# dpsv2.net
KiCad netlist of a schematic drawn in EAGLE
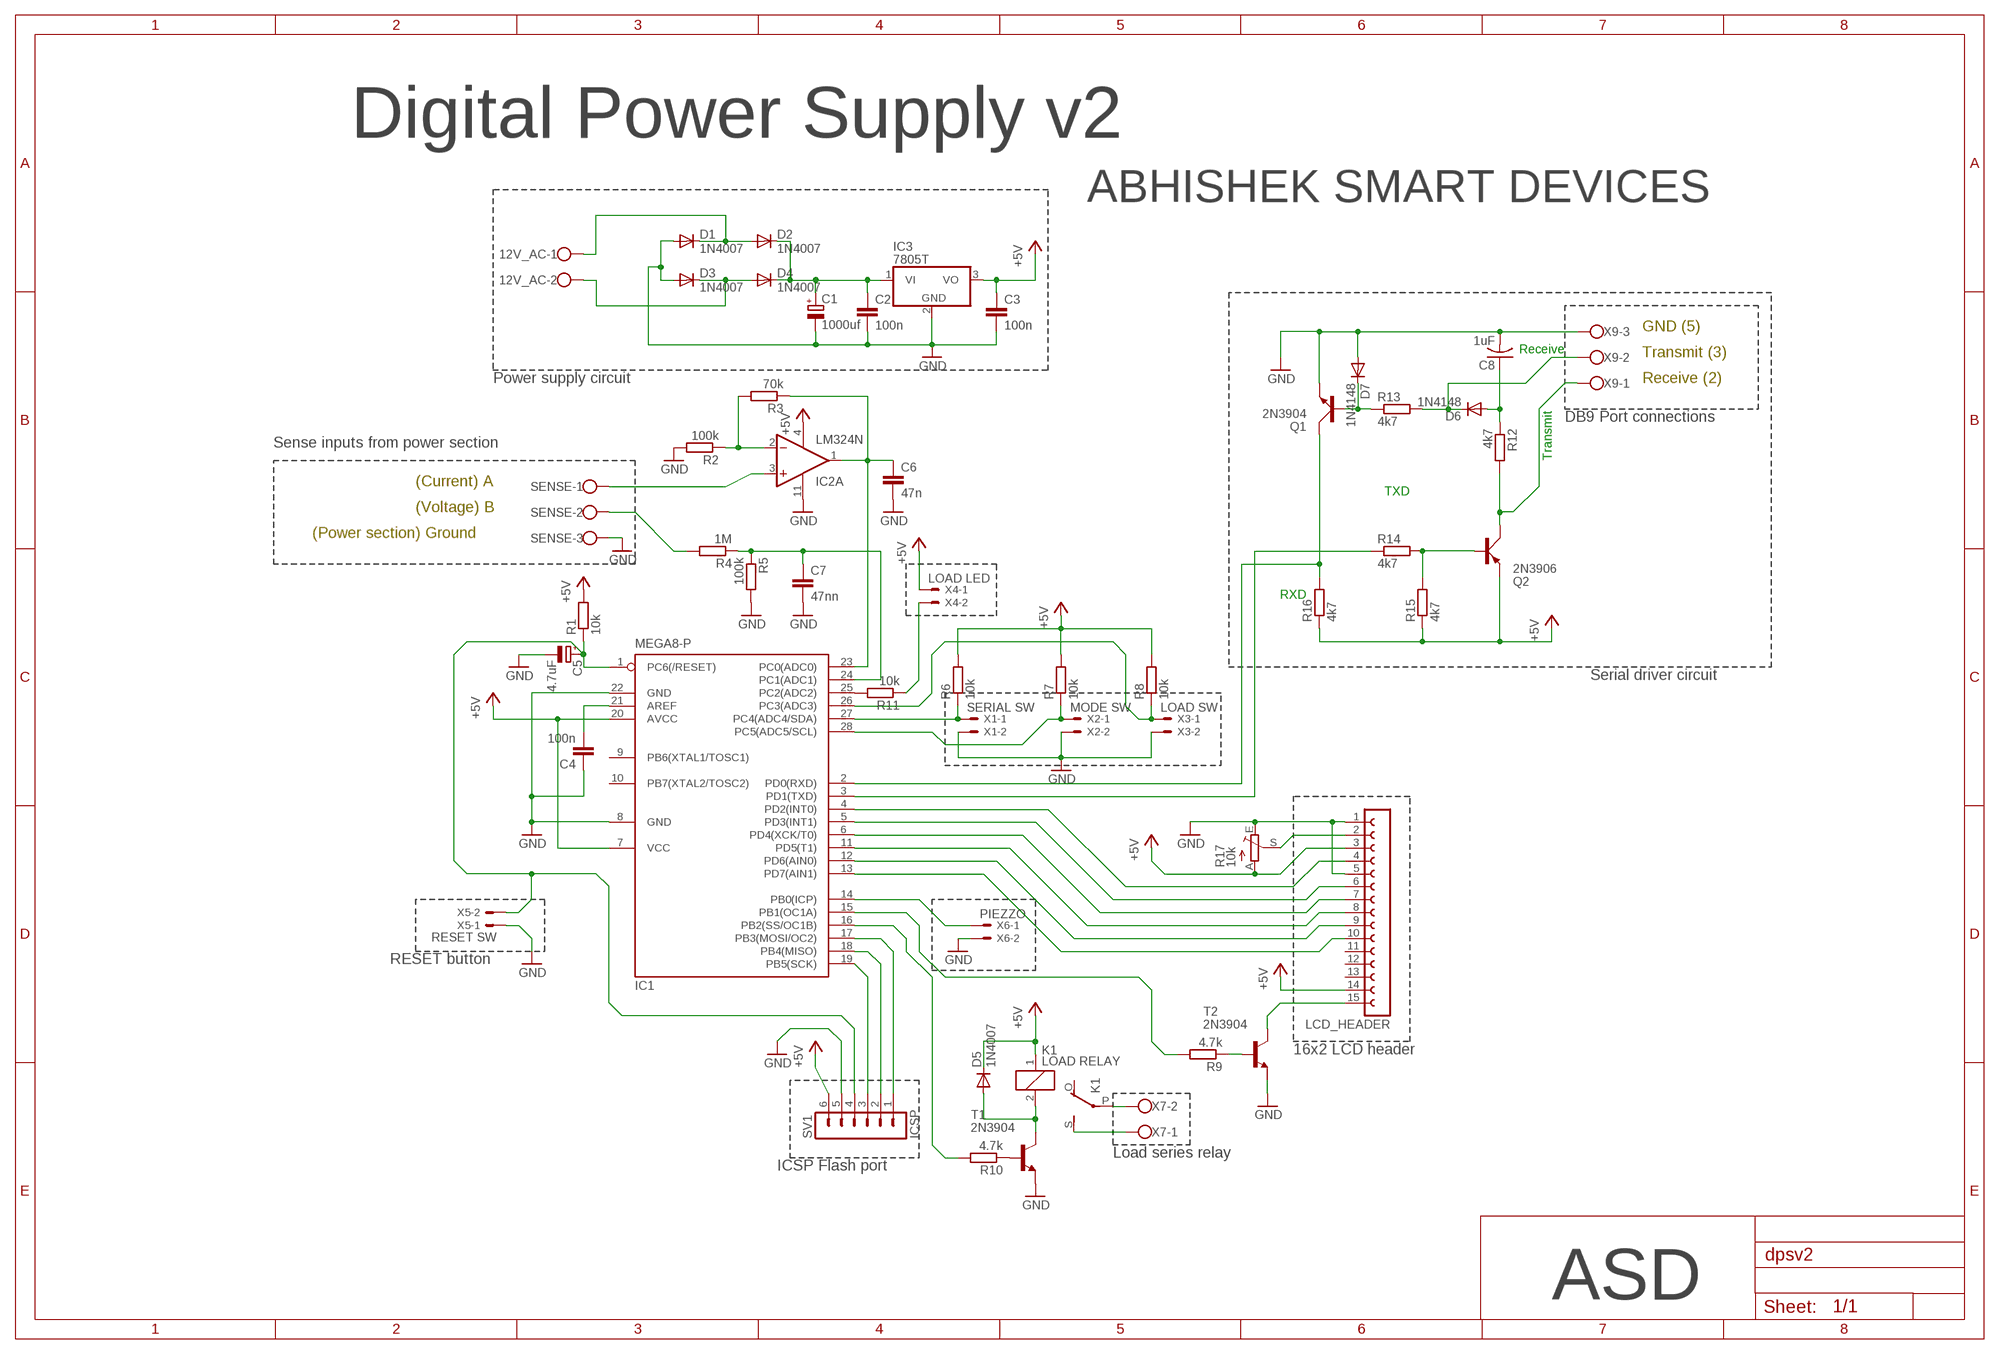
[diagram p0: schematic, sheet 1]

(export (version "E")
  (design (tool "Eeschema 10.0.6"))
  (components
    (comp (ref "12V_AC")
      (value "W237-102")
      (footprint "eagle-import:W237-102")
      (fields (field (name "MPN") "237-102"))
      (libsource (lib "eagle-import") (part "W237-102"))
    )
    (comp (ref "C1")
      (value "1000uf")
      (footprint "eagle-import:E5-13")
      (libsource (lib "eagle-import") (part "CPOL-EUE5-13"))
    )
    (comp (ref "C2")
      (value "100n")
      (footprint "eagle-import:C102-054X133")
      (libsource (lib "eagle-import") (part "C-EU102-054X133"))
    )
    (comp (ref "C3")
      (value "100n")
      (footprint "eagle-import:C102-054X133")
      (libsource (lib "eagle-import") (part "C-EU102-054X133"))
    )
    (comp (ref "C4")
      (value "100n")
      (footprint "eagle-import:C102-054X133")
      (libsource (lib "eagle-import") (part "C-EU102-054X133"))
    )
    (comp (ref "C5")
      (value "4.7uF")
      (footprint "eagle-import:E2,5-7")
      (libsource (lib "eagle-import") (part "CPOL-EUE2.5-7"))
    )
    (comp (ref "C6")
      (value "47n")
      (footprint "eagle-import:C050-025X075")
      (libsource (lib "eagle-import") (part "C-EU050-025X075"))
    )
    (comp (ref "C7")
      (value "47nn")
      (footprint "eagle-import:C050-025X075")
      (libsource (lib "eagle-import") (part "C-EU050-025X075"))
    )
    (comp (ref "C8")
      (value "1uF")
      (footprint "eagle-import:C025-040X050")
      (libsource (lib "eagle-import") (part "C-US025-040X050"))
    )
    (comp (ref "D1")
      (value "1N4007")
      (footprint "eagle-import:DO07")
      (libsource (lib "eagle-import") (part "DIODE-DO07"))
    )
    (comp (ref "D2")
      (value "1N4007")
      (footprint "eagle-import:DO07")
      (libsource (lib "eagle-import") (part "DIODE-DO07"))
    )
    (comp (ref "D3")
      (value "1N4007")
      (footprint "eagle-import:DO07")
      (libsource (lib "eagle-import") (part "DIODE-DO07"))
    )
    (comp (ref "D4")
      (value "1N4007")
      (footprint "eagle-import:DO07")
      (libsource (lib "eagle-import") (part "DIODE-DO07"))
    )
    (comp (ref "D5")
      (value "1N4007")
      (footprint "eagle-import:DO07")
      (libsource (lib "eagle-import") (part "DIODE-DO07"))
    )
    (comp (ref "D6")
      (value "1N4148")
      (footprint "eagle-import:DO35-10")
      (libsource (lib "eagle-import") (part "1N4148"))
    )
    (comp (ref "D7")
      (value "1N4148")
      (footprint "eagle-import:DO35-10")
      (libsource (lib "eagle-import") (part "1N4148"))
    )
    (comp (ref "IC1")
      (value "MEGA8-P")
      (footprint "eagle-import:DIL28-3")
      (libsource (lib "eagle-import") (part "MEGA8-P"))
    )
    (comp (ref "IC2")
      (value "LM324N")
      (footprint "eagle-import:DIL14")
      (libsource (lib "eagle-import") (part "LM324N"))
    )
    (comp (ref "IC3")
      (value "7805T")
      (footprint "eagle-import:TO220H")
      (libsource (lib "eagle-import") (part "78T05"))
    )
    (comp (ref "K1")
      (value "LOAD RELAY")
      (footprint "eagle-import:G5LE")
      (libsource (lib "eagle-import") (part "G5L"))
    )
    (comp (ref "LCD_HEADER")
      (value "FE15-1")
      (footprint "eagle-import:FE15")
      (libsource (lib "eagle-import") (part "FE15-1"))
    )
    (comp (ref "Q1")
      (value "2N3904")
      (footprint "eagle-import:TO92D")
      (libsource (lib "eagle-import") (part "2N3904"))
    )
    (comp (ref "Q2")
      (value "2N3906")
      (footprint "eagle-import:TO92D")
      (libsource (lib "eagle-import") (part "2N3906"))
    )
    (comp (ref "R1")
      (value "10k")
      (footprint "eagle-import:0309_12")
      (libsource (lib "eagle-import") (part "R-EU_0309/12"))
    )
    (comp (ref "R2")
      (value "100k")
      (footprint "eagle-import:0309_12")
      (libsource (lib "eagle-import") (part "R-EU_0309/12"))
    )
    (comp (ref "R3")
      (value "70k")
      (footprint "eagle-import:0309_12")
      (libsource (lib "eagle-import") (part "R-EU_0309/12"))
    )
    (comp (ref "R4")
      (value "1M")
      (footprint "eagle-import:0309_12")
      (libsource (lib "eagle-import") (part "R-EU_0309/12"))
    )
    (comp (ref "R5")
      (value "100k")
      (footprint "eagle-import:0309_12")
      (libsource (lib "eagle-import") (part "R-EU_0309/12"))
    )
    (comp (ref "R6")
      (value "10k")
      (footprint "eagle-import:0309_12")
      (libsource (lib "eagle-import") (part "R-EU_0309/12"))
    )
    (comp (ref "R7")
      (value "10k")
      (footprint "eagle-import:0309_12")
      (libsource (lib "eagle-import") (part "R-EU_0309/12"))
    )
    (comp (ref "R8")
      (value "10k")
      (footprint "eagle-import:0309_12")
      (libsource (lib "eagle-import") (part "R-EU_0309/12"))
    )
    (comp (ref "R9")
      (value "4.7k")
      (footprint "eagle-import:0309_12")
      (libsource (lib "eagle-import") (part "R-EU_0309/12"))
    )
    (comp (ref "R10")
      (value "4.7k")
      (footprint "eagle-import:0309_12")
      (libsource (lib "eagle-import") (part "R-EU_0309/12"))
    )
    (comp (ref "R11")
      (value "10k")
      (footprint "eagle-import:0309_12")
      (libsource (lib "eagle-import") (part "R-EU_0309/12"))
    )
    (comp (ref "R12")
      (value "4k7")
      (footprint "eagle-import:0309_12")
      (libsource (lib "eagle-import") (part "R-EU_0309/12"))
    )
    (comp (ref "R13")
      (value "4k7")
      (footprint "eagle-import:0309_12")
      (libsource (lib "eagle-import") (part "R-EU_0309/12"))
    )
    (comp (ref "R14")
      (value "4k7")
      (footprint "eagle-import:0309_12")
      (libsource (lib "eagle-import") (part "R-EU_0309/12"))
    )
    (comp (ref "R15")
      (value "4k7")
      (footprint "eagle-import:0309_12")
      (libsource (lib "eagle-import") (part "R-EU_0309/12"))
    )
    (comp (ref "R16")
      (value "4k7")
      (footprint "eagle-import:0309_12")
      (libsource (lib "eagle-import") (part "R-EU_0309/12"))
    )
    (comp (ref "R17")
      (value "10k")
      (footprint "eagle-import:B25X")
      (libsource (lib "eagle-import") (part "TRIM_EU-B25X"))
    )
    (comp (ref "SENSE")
      (value "W237-103")
      (footprint "eagle-import:W237-103")
      (fields (field (name "MPN") "237-103"))
      (libsource (lib "eagle-import") (part "W237-103"))
    )
    (comp (ref "SV1")
      (value "ICSP")
      (footprint "eagle-import:MA06-1")
      (libsource (lib "eagle-import") (part "MA06-1"))
    )
    (comp (ref "T1")
      (value "2N3904")
      (footprint "eagle-import:TO92-CBE")
      (libsource (lib "eagle-import") (part "-NPN-TO92-CBEBC548"))
    )
    (comp (ref "T2")
      (value "2N3904")
      (footprint "eagle-import:TO92-CBE")
      (libsource (lib "eagle-import") (part "-NPN-TO92-CBEBC548"))
    )
    (comp (ref "X1")
      (value "SERIAL SW")
      (footprint "eagle-import:22-23-2021")
      (fields (field (name "MF") "MOLEX") (field (name "MPN") "22-23-2021"))
      (libsource (lib "eagle-import") (part "22-23-2021"))
    )
    (comp (ref "X2")
      (value "MODE SW")
      (footprint "eagle-import:22-23-2021")
      (fields (field (name "MF") "MOLEX") (field (name "MPN") "22-23-2021"))
      (libsource (lib "eagle-import") (part "22-23-2021"))
    )
    (comp (ref "X3")
      (value "LOAD SW")
      (footprint "eagle-import:22-23-2021")
      (fields (field (name "MF") "MOLEX") (field (name "MPN") "22-23-2021"))
      (libsource (lib "eagle-import") (part "22-23-2021"))
    )
    (comp (ref "X4")
      (value "LOAD LED")
      (footprint "eagle-import:22-23-2021")
      (fields (field (name "MF") "MOLEX") (field (name "MPN") "22-23-2021"))
      (libsource (lib "eagle-import") (part "22-23-2021"))
    )
    (comp (ref "X5")
      (value "RESET SW")
      (footprint "eagle-import:22-23-2021")
      (fields (field (name "MF") "MOLEX") (field (name "MPN") "22-23-2021"))
      (libsource (lib "eagle-import") (part "22-23-2021"))
    )
    (comp (ref "X6")
      (value "PIEZZO")
      (footprint "eagle-import:22-23-2021")
      (fields (field (name "MF") "MOLEX") (field (name "MPN") "22-23-2021"))
      (libsource (lib "eagle-import") (part "22-23-2021"))
    )
    (comp (ref "X7")
      (value "W237-102")
      (footprint "eagle-import:W237-102")
      (fields (field (name "MPN") "237-102"))
      (libsource (lib "eagle-import") (part "W237-102"))
    )
    (comp (ref "X9")
      (value "W237-103")
      (footprint "eagle-import:W237-103")
      (fields (field (name "MPN") "237-103"))
      (libsource (lib "eagle-import") (part "W237-103"))
    )
  )
  (nets
    (net (code "1") (name "+5V") (class "Default")
      (node (ref "C3") (pin "1") (pinfunction "1_1") (pintype "passive"))
      (node (ref "D5") (pin "C") (pinfunction "C_C") (pintype "passive"))
      (node (ref "IC1") (pin "20") (pinfunction "AVCC_20") (pintype "power_in"))
      (node (ref "IC1") (pin "7") (pinfunction "VCC_7") (pintype "power_in"))
      (node (ref "IC2") (pin "4") (pinfunction "V+_4") (pintype "power_in"))
      (node (ref "IC3") (pin "3") (pinfunction "VO_3") (pintype "passive"))
      (node (ref "K1") (pin "1") (pinfunction "1_1") (pintype "passive"))
      (node (ref "LCD_HEADER") (pin "14") (pinfunction "14_14") (pintype "passive"))
      (node (ref "LCD_HEADER") (pin "3") (pinfunction "3_3") (pintype "passive"))
      (node (ref "Q2") (pin "E") (pinfunction "E_E") (pintype "passive"))
      (node (ref "R1") (pin "2") (pinfunction "2_2") (pintype "passive"))
      (node (ref "R15") (pin "1") (pinfunction "1_1") (pintype "passive"))
      (node (ref "R16") (pin "1") (pinfunction "1_1") (pintype "passive"))
      (node (ref "R17") (pin "A") (pinfunction "A_A") (pintype "passive"))
      (node (ref "R6") (pin "2") (pinfunction "2_2") (pintype "passive"))
      (node (ref "R7") (pin "2") (pinfunction "2_2") (pintype "passive"))
      (node (ref "R8") (pin "2") (pinfunction "2_2") (pintype "passive"))
      (node (ref "SV1") (pin "6") (pinfunction "6_6") (pintype "passive"))
      (node (ref "X4") (pin "1") (pinfunction "S_1") (pintype "passive"))
    )
    (net (code "2") (name "GND") (class "Default")
      (node (ref "C1") (pin "-") (pinfunction "-_-") (pintype "passive"))
      (node (ref "C2") (pin "2") (pinfunction "2_2") (pintype "passive"))
      (node (ref "C3") (pin "2") (pinfunction "2_2") (pintype "passive"))
      (node (ref "C4") (pin "1") (pinfunction "1_1") (pintype "passive"))
      (node (ref "C5") (pin "-") (pinfunction "-_-") (pintype "passive"))
      (node (ref "C6") (pin "2") (pinfunction "2_2") (pintype "passive"))
      (node (ref "C7") (pin "2") (pinfunction "2_2") (pintype "passive"))
      (node (ref "C8") (pin "2") (pinfunction "2_2") (pintype "passive"))
      (node (ref "D1") (pin "A") (pinfunction "A_A") (pintype "passive"))
      (node (ref "D3") (pin "A") (pinfunction "A_A") (pintype "passive"))
      (node (ref "D7") (pin "A") (pinfunction "A_A") (pintype "passive"))
      (node (ref "IC1") (pin "22") (pinfunction "GND_22") (pintype "power_in"))
      (node (ref "IC1") (pin "8") (pinfunction "GND_8") (pintype "power_in"))
      (node (ref "IC2") (pin "11") (pinfunction "V-_11") (pintype "power_in"))
      (node (ref "IC3") (pin "2") (pinfunction "GND_2") (pintype "passive"))
      (node (ref "LCD_HEADER") (pin "1") (pinfunction "1_1") (pintype "passive"))
      (node (ref "LCD_HEADER") (pin "5") (pinfunction "5_5") (pintype "passive"))
      (node (ref "Q1") (pin "E") (pinfunction "E_E") (pintype "passive"))
      (node (ref "R17") (pin "E") (pinfunction "E_E") (pintype "passive"))
      (node (ref "R2") (pin "2") (pinfunction "2_2") (pintype "passive"))
      (node (ref "R5") (pin "2") (pinfunction "2_2") (pintype "passive"))
      (node (ref "SENSE") (pin "3") (pinfunction "KL_3") (pintype "passive"))
      (node (ref "SV1") (pin "5") (pinfunction "5_5") (pintype "passive"))
      (node (ref "T1") (pin "E") (pinfunction "E_E") (pintype "passive"))
      (node (ref "T2") (pin "E") (pinfunction "E_E") (pintype "passive"))
      (node (ref "X1") (pin "2") (pinfunction "S_2") (pintype "passive"))
      (node (ref "X2") (pin "2") (pinfunction "S_2") (pintype "passive"))
      (node (ref "X3") (pin "2") (pinfunction "S_2") (pintype "passive"))
      (node (ref "X5") (pin "1") (pinfunction "S_1") (pintype "passive"))
      (node (ref "X6") (pin "2") (pinfunction "S_2") (pintype "passive"))
      (node (ref "X9") (pin "3") (pinfunction "KL_3") (pintype "passive"))
    )
    (net (code "3") (name "Net-(12V_ACA-KL)") (class "Default")
      (node (ref "12V_AC") (pin "1") (pinfunction "KL_1") (pintype "passive"))
      (node (ref "D1") (pin "C") (pinfunction "C_C") (pintype "passive"))
      (node (ref "D2") (pin "A") (pinfunction "A_A") (pintype "passive"))
    )
    (net (code "4") (name "Net-(12V_ACB-KL)") (class "Default")
      (node (ref "12V_AC") (pin "2") (pinfunction "KL_2") (pintype "passive"))
      (node (ref "D3") (pin "C") (pinfunction "C_C") (pintype "passive"))
      (node (ref "D4") (pin "A") (pinfunction "A_A") (pintype "passive"))
    )
    (net (code "5") (name "Net-(C8-Pad1)") (class "Default")
      (node (ref "C8") (pin "1") (pinfunction "1_1") (pintype "passive"))
      (node (ref "D6") (pin "A") (pinfunction "A_A") (pintype "passive"))
      (node (ref "R12") (pin "1") (pinfunction "1_1") (pintype "passive"))
    )
    (net (code "6") (name "Net-(D5-PadA)") (class "Default")
      (node (ref "D5") (pin "A") (pinfunction "A_A") (pintype "passive"))
      (node (ref "K1") (pin "2") (pinfunction "2_2") (pintype "passive"))
      (node (ref "T1") (pin "C") (pinfunction "C_C") (pintype "passive"))
    )
    (net (code "7") (name "Net-(D7-PadC)") (class "Default")
      (node (ref "D7") (pin "C") (pinfunction "C_C") (pintype "passive"))
      (node (ref "Q1") (pin "B") (pinfunction "B_B") (pintype "passive"))
      (node (ref "R13") (pin "1") (pinfunction "1_1") (pintype "passive"))
    )
    (net (code "8") (name "Net-(IC1-AREF)") (class "Default")
      (node (ref "C4") (pin "2") (pinfunction "2_2") (pintype "passive"))
      (node (ref "IC1") (pin "21") (pinfunction "AREF_21") (pintype "passive"))
    )
    (net (code "9") (name "Net-(IC1-PB0(ICP))") (class "Default")
      (node (ref "IC1") (pin "14") (pinfunction "PB0(ICP)_14") (pintype "bidirectional"))
      (node (ref "X6") (pin "1") (pinfunction "S_1") (pintype "passive"))
    )
    (net (code "10") (name "Net-(IC1-PB1(OC1A))") (class "Default")
      (node (ref "IC1") (pin "15") (pinfunction "PB1(OC1A)_15") (pintype "bidirectional"))
      (node (ref "R9") (pin "2") (pinfunction "2_2") (pintype "passive"))
    )
    (net (code "11") (name "Net-(IC1-PB2(SS{slash}OC1B))") (class "Default")
      (node (ref "IC1") (pin "16") (pinfunction "PB2(SS/OC1B)_16") (pintype "bidirectional"))
      (node (ref "R10") (pin "2") (pinfunction "2_2") (pintype "passive"))
    )
    (net (code "12") (name "Net-(IC1-PB3(MOSI{slash}OC2))") (class "Default")
      (node (ref "IC1") (pin "17") (pinfunction "PB3(MOSI/OC2)_17") (pintype "bidirectional"))
      (node (ref "SV1") (pin "1") (pinfunction "1_1") (pintype "passive"))
    )
    (net (code "13") (name "Net-(IC1-PB4(MISO))") (class "Default")
      (node (ref "IC1") (pin "18") (pinfunction "PB4(MISO)_18") (pintype "bidirectional"))
      (node (ref "SV1") (pin "2") (pinfunction "2_2") (pintype "passive"))
    )
    (net (code "14") (name "Net-(IC1-PB5(SCK))") (class "Default")
      (node (ref "IC1") (pin "19") (pinfunction "PB5(SCK)_19") (pintype "bidirectional"))
      (node (ref "SV1") (pin "3") (pinfunction "3_3") (pintype "passive"))
    )
    (net (code "15") (name "Net-(IC1-PC0(ADC0))") (class "Default")
      (node (ref "C6") (pin "1") (pinfunction "1_1") (pintype "passive"))
      (node (ref "IC1") (pin "23") (pinfunction "PC0(ADC0)_23") (pintype "bidirectional"))
      (node (ref "IC2") (pin "1") (pinfunction "OUT_1") (pintype "output"))
      (node (ref "R3") (pin "1") (pinfunction "1_1") (pintype "passive"))
    )
    (net (code "16") (name "Net-(IC1-PC1(ADC1))") (class "Default")
      (node (ref "C7") (pin "1") (pinfunction "1_1") (pintype "passive"))
      (node (ref "IC1") (pin "24") (pinfunction "PC1(ADC1)_24") (pintype "bidirectional"))
      (node (ref "R4") (pin "1") (pinfunction "1_1") (pintype "passive"))
      (node (ref "R5") (pin "1") (pinfunction "1_1") (pintype "passive"))
    )
    (net (code "17") (name "Net-(IC1-PC2(ADC2))") (class "Default")
      (node (ref "IC1") (pin "25") (pinfunction "PC2(ADC2)_25") (pintype "bidirectional"))
      (node (ref "R11") (pin "2") (pinfunction "2_2") (pintype "passive"))
    )
    (net (code "18") (name "Net-(IC1-PC3(ADC3))") (class "Default")
      (node (ref "IC1") (pin "26") (pinfunction "PC3(ADC3)_26") (pintype "bidirectional"))
      (node (ref "R8") (pin "1") (pinfunction "1_1") (pintype "passive"))
      (node (ref "X3") (pin "1") (pinfunction "S_1") (pintype "passive"))
    )
    (net (code "19") (name "Net-(IC1-PC4(ADC4{slash}SDA))") (class "Default")
      (node (ref "IC1") (pin "27") (pinfunction "PC4(ADC4/SDA)_27") (pintype "bidirectional"))
      (node (ref "R6") (pin "1") (pinfunction "1_1") (pintype "passive"))
      (node (ref "X1") (pin "1") (pinfunction "S_1") (pintype "passive"))
    )
    (net (code "20") (name "Net-(IC1-PC5(ADC5{slash}SCL))") (class "Default")
      (node (ref "IC1") (pin "28") (pinfunction "PC5(ADC5/SCL)_28") (pintype "bidirectional"))
      (node (ref "R7") (pin "1") (pinfunction "1_1") (pintype "passive"))
      (node (ref "X2") (pin "1") (pinfunction "S_1") (pintype "passive"))
    )
    (net (code "21") (name "Net-(IC1-PC6({slash}RESET))") (class "Default")
      (node (ref "C5") (pin "+") (pinfunction "+_+") (pintype "passive"))
      (node (ref "IC1") (pin "1") (pinfunction "PC6(/RESET)_1") (pintype "bidirectional"))
      (node (ref "R1") (pin "1") (pinfunction "1_1") (pintype "passive"))
      (node (ref "SV1") (pin "4") (pinfunction "4_4") (pintype "passive"))
      (node (ref "X5") (pin "2") (pinfunction "S_2") (pintype "passive"))
    )
    (net (code "22") (name "Net-(IC1-PD0(RXD))") (class "Default")
      (node (ref "IC1") (pin "2") (pinfunction "PD0(RXD)_2") (pintype "bidirectional"))
      (node (ref "Q1") (pin "C") (pinfunction "C_C") (pintype "passive"))
      (node (ref "R16") (pin "2") (pinfunction "2_2") (pintype "passive"))
    )
    (net (code "23") (name "Net-(IC1-PD1(TXD))") (class "Default")
      (node (ref "IC1") (pin "3") (pinfunction "PD1(TXD)_3") (pintype "bidirectional"))
      (node (ref "R14") (pin "1") (pinfunction "1_1") (pintype "passive"))
    )
    (net (code "24") (name "Net-(IC1-PD2(INT0))") (class "Default")
      (node (ref "IC1") (pin "4") (pinfunction "PD2(INT0)_4") (pintype "bidirectional"))
      (node (ref "LCD_HEADER") (pin "4") (pinfunction "4_4") (pintype "passive"))
    )
    (net (code "25") (name "Net-(IC1-PD3(INT1))") (class "Default")
      (node (ref "IC1") (pin "5") (pinfunction "PD3(INT1)_5") (pintype "bidirectional"))
      (node (ref "LCD_HEADER") (pin "6") (pinfunction "6_6") (pintype "passive"))
    )
    (net (code "26") (name "Net-(IC1-PD4(XCK{slash}T0))") (class "Default")
      (node (ref "IC1") (pin "6") (pinfunction "PD4(XCK/T0)_6") (pintype "bidirectional"))
      (node (ref "LCD_HEADER") (pin "7") (pinfunction "7_7") (pintype "passive"))
    )
    (net (code "27") (name "Net-(IC1-PD5(T1))") (class "Default")
      (node (ref "IC1") (pin "11") (pinfunction "PD5(T1)_11") (pintype "bidirectional"))
      (node (ref "LCD_HEADER") (pin "8") (pinfunction "8_8") (pintype "passive"))
    )
    (net (code "28") (name "Net-(IC1-PD6(AIN0))") (class "Default")
      (node (ref "IC1") (pin "12") (pinfunction "PD6(AIN0)_12") (pintype "bidirectional"))
      (node (ref "LCD_HEADER") (pin "9") (pinfunction "9_9") (pintype "passive"))
    )
    (net (code "29") (name "Net-(IC1-PD7(AIN1))") (class "Default")
      (node (ref "IC1") (pin "13") (pinfunction "PD7(AIN1)_13") (pintype "bidirectional"))
      (node (ref "LCD_HEADER") (pin "10") (pinfunction "10_10") (pintype "passive"))
    )
    (net (code "30") (name "Net-(IC2A-+IN)") (class "Default")
      (node (ref "IC2") (pin "3") (pinfunction "+IN_3") (pintype "input"))
      (node (ref "SENSE") (pin "1") (pinfunction "KL_1") (pintype "passive"))
    )
    (net (code "31") (name "Net-(IC2A--IN)") (class "Default")
      (node (ref "IC2") (pin "2") (pinfunction "-IN_2") (pintype "input"))
      (node (ref "R2") (pin "1") (pinfunction "1_1") (pintype "passive"))
      (node (ref "R3") (pin "2") (pinfunction "2_2") (pintype "passive"))
    )
    (net (code "32") (name "Net-(IC3-VI)") (class "Default")
      (node (ref "C1") (pin "+") (pinfunction "+_+") (pintype "passive"))
      (node (ref "C2") (pin "1") (pinfunction "1_1") (pintype "passive"))
      (node (ref "D2") (pin "C") (pinfunction "C_C") (pintype "passive"))
      (node (ref "D4") (pin "C") (pinfunction "C_C") (pintype "passive"))
      (node (ref "IC3") (pin "1") (pinfunction "VI_1") (pintype "input"))
    )
    (net (code "33") (name "Net-(LCD_HEADER-Pad2)") (class "Default")
      (node (ref "LCD_HEADER") (pin "2") (pinfunction "2_2") (pintype "passive"))
      (node (ref "R17") (pin "S") (pinfunction "S_S") (pintype "passive"))
    )
    (net (code "34") (name "Net-(LCD_HEADER-Pad15)") (class "Default")
      (node (ref "LCD_HEADER") (pin "15") (pinfunction "15_15") (pintype "passive"))
      (node (ref "T2") (pin "C") (pinfunction "C_C") (pintype "passive"))
    )
    (net (code "35") (name "Net-(Q2-PadB)") (class "Default")
      (node (ref "Q2") (pin "B") (pinfunction "B_B") (pintype "passive"))
      (node (ref "R14") (pin "2") (pinfunction "2_2") (pintype "passive"))
      (node (ref "R15") (pin "2") (pinfunction "2_2") (pintype "passive"))
    )
    (net (code "36") (name "Net-(R9-Pad1)") (class "Default")
      (node (ref "R9") (pin "1") (pinfunction "1_1") (pintype "passive"))
      (node (ref "T2") (pin "B") (pinfunction "B_B") (pintype "passive"))
    )
    (net (code "37") (name "Net-(R10-Pad1)") (class "Default")
      (node (ref "R10") (pin "1") (pinfunction "1_1") (pintype "passive"))
      (node (ref "T1") (pin "B") (pinfunction "B_B") (pintype "passive"))
    )
    (net (code "38") (name "Net-(SENSEB-KL)") (class "Default")
      (node (ref "R4") (pin "2") (pinfunction "2_2") (pintype "passive"))
      (node (ref "SENSE") (pin "2") (pinfunction "KL_2") (pintype "passive"))
    )
    (net (code "39") (name "Net-(X4B-S)") (class "Default")
      (node (ref "R11") (pin "1") (pinfunction "1_1") (pintype "passive"))
      (node (ref "X4") (pin "2") (pinfunction "S_2") (pintype "passive"))
    )
    (net (code "40") (name "Net-(X7A-KL)") (class "Default")
      (node (ref "K1") (pin "S") (pinfunction "S_S") (pintype "passive"))
      (node (ref "X7") (pin "1") (pinfunction "KL_1") (pintype "passive"))
    )
    (net (code "41") (name "Net-(X7B-KL)") (class "Default")
      (node (ref "K1") (pin "P") (pinfunction "P_P") (pintype "passive"))
      (node (ref "X7") (pin "2") (pinfunction "KL_2") (pintype "passive"))
    )
    (net (code "42") (name "Net-(X9A-KL)") (class "Default")
      (node (ref "Q2") (pin "C") (pinfunction "C_C") (pintype "passive"))
      (node (ref "R12") (pin "2") (pinfunction "2_2") (pintype "passive"))
      (node (ref "X9") (pin "1") (pinfunction "KL_1") (pintype "passive"))
    )
    (net (code "43") (name "Net-(X9B-KL)") (class "Default")
      (node (ref "D6") (pin "C") (pinfunction "C_C") (pintype "passive"))
      (node (ref "R13") (pin "2") (pinfunction "2_2") (pintype "passive"))
      (node (ref "X9") (pin "2") (pinfunction "KL_2") (pintype "passive"))
    )
    (net (code "44") (name "unconnected-(IC1-PB6(XTAL1{slash}TOSC1)-Pad9)") (class "Default")
      (node (ref "IC1") (pin "9") (pinfunction "PB6(XTAL1/TOSC1)_9") (pintype "bidirectional"))
    )
    (net (code "45") (name "unconnected-(IC1-PB7(XTAL2{slash}TOSC2)-Pad10)") (class "Default")
      (node (ref "IC1") (pin "10") (pinfunction "PB7(XTAL2/TOSC2)_10") (pintype "bidirectional"))
    )
    (net (code "46") (name "unconnected-(K1-PadO)") (class "Default")
      (node (ref "K1") (pin "O") (pinfunction "O_O") (pintype "passive"))
    )
    (net (code "47") (name "unconnected-(LCD_HEADER-Pad11)") (class "Default")
      (node (ref "LCD_HEADER") (pin "11") (pinfunction "11_11") (pintype "passive"))
    )
    (net (code "48") (name "unconnected-(LCD_HEADER-Pad12)") (class "Default")
      (node (ref "LCD_HEADER") (pin "12") (pinfunction "12_12") (pintype "passive"))
    )
    (net (code "49") (name "unconnected-(LCD_HEADER-Pad13)") (class "Default")
      (node (ref "LCD_HEADER") (pin "13") (pinfunction "13_13") (pintype "passive"))
    )
  )
)
